# cpu.net
KiCad netlist of a schematic drawn in Altium Designer
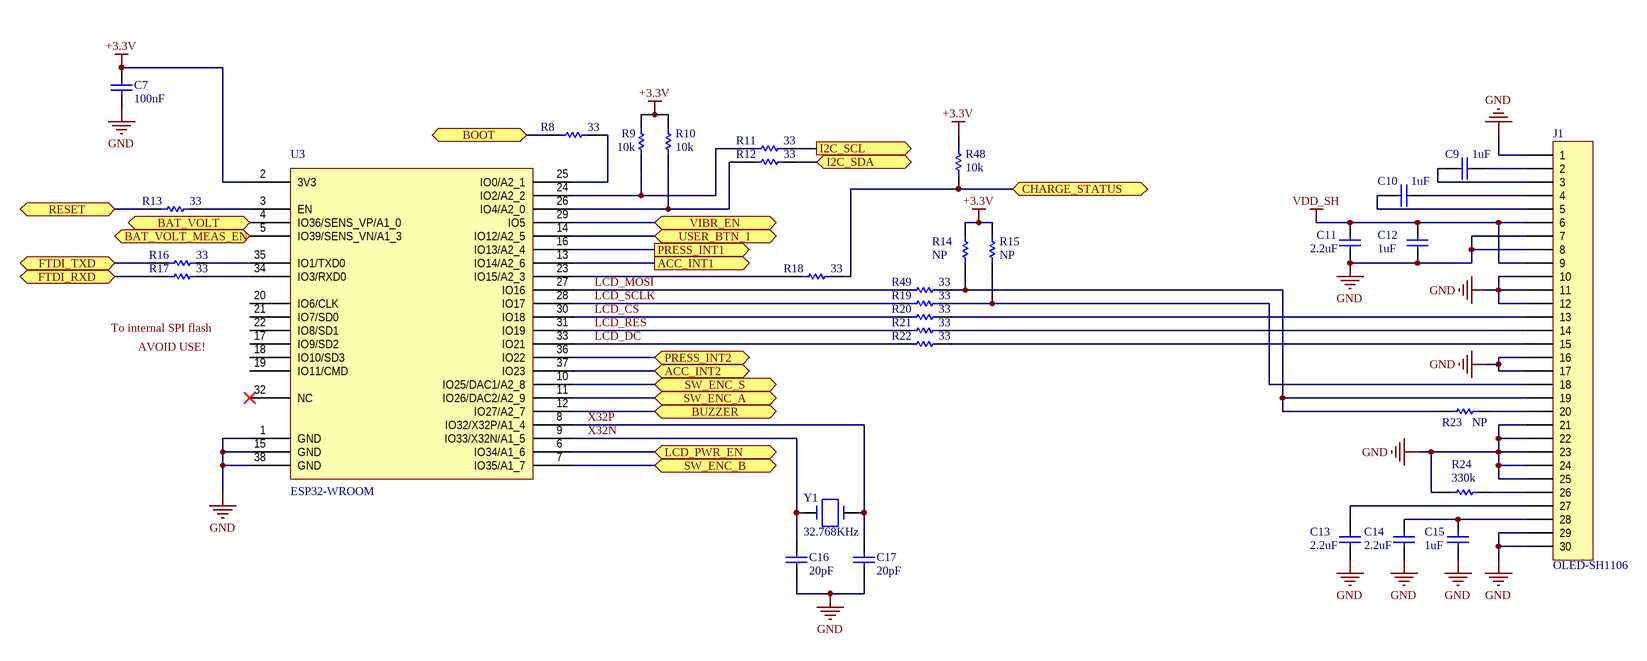
[diagram p0: cpu.SchDoc]

(export (version "E")
  (design (tool "Eeschema 10.0.6"))
  (components
    (comp (ref "C7")
      (value "100nF")
      (footprint "0402_[1005]")
      (description "Capacitor")
      (fields (field (name "PUBLISHER") "Altium Limited"))
      (libsource (lib "Miscellaneous Devices") (part "Cap"))
    )
    (comp (ref "C9")
      (value "1uF")
      (footprint "0603_[1608]")
      (description "Capacitor")
      (fields (field (name "PUBLISHER") "Altium Limited"))
      (libsource (lib "develer_library") (part "Cap"))
    )
    (comp (ref "C10")
      (value "1uF")
      (footprint "0603_[1608]")
      (description "Capacitor")
      (fields (field (name "PUBLISHER") "Altium Limited"))
      (libsource (lib "develer_library") (part "Cap"))
    )
    (comp (ref "C11")
      (value "2.2uF")
      (footprint "0603_[1608]")
      (description "Capacitor")
      (fields (field (name "PUBLISHER") "Altium Limited"))
      (libsource (lib "develer_library") (part "Cap"))
    )
    (comp (ref "C12")
      (value "1uF")
      (footprint "0603_[1608]")
      (description "Capacitor")
      (fields (field (name "PUBLISHER") "Altium Limited"))
      (libsource (lib "develer_library") (part "Cap"))
    )
    (comp (ref "C13")
      (value "2.2uF")
      (footprint "0603_[1608]")
      (description "Capacitor")
      (fields (field (name "PUBLISHER") "Altium Limited"))
      (libsource (lib "develer_library") (part "Cap"))
    )
    (comp (ref "C14")
      (value "2.2uF")
      (footprint "0603_[1608]")
      (description "Capacitor")
      (fields (field (name "PUBLISHER") "Altium Limited"))
      (libsource (lib "develer_library") (part "Cap"))
    )
    (comp (ref "C15")
      (value "1uF")
      (footprint "0603_[1608]")
      (description "Capacitor")
      (fields (field (name "PUBLISHER") "Altium Limited"))
      (libsource (lib "develer_library") (part "Cap"))
    )
    (comp (ref "C16")
      (value "20pF")
      (footprint "0402_[1005]")
      (description "Capacitor")
      (fields (field (name "PUBLISHER") "Altium Limited"))
      (libsource (lib "develer_library") (part "Cap"))
    )
    (comp (ref "C17")
      (value "20pF")
      (footprint "0402_[1005]")
      (description "Capacitor")
      (fields (field (name "PUBLISHER") "Altium Limited"))
      (libsource (lib "develer_library") (part "Cap"))
    )
    (comp (ref "J1")
      (value "OLED-SH1106")
      (footprint "flat_30pin_0,7mm")
      (description "Header, 30-Pin")
      (fields (field (name "PUBLISHER") "Altium Limited"))
      (libsource (lib "Miscellaneous Connectors") (part "Header 30"))
    )
    (comp (ref "R8")
      (value "33")
      (footprint "0402_[1005]")
      (description "Resistor")
      (fields (field (name "PUBLISHER") "Altium Limited"))
      (libsource (lib "Miscellaneous Devices") (part "Res1"))
    )
    (comp (ref "R9")
      (value "10k")
      (footprint "0402_[1005]")
      (description "Resistor")
      (fields (field (name "PUBLISHER") "Altium Limited"))
      (libsource (lib "Miscellaneous Devices") (part "Res1"))
    )
    (comp (ref "R10")
      (value "10k")
      (footprint "0402_[1005]")
      (description "Resistor")
      (fields (field (name "PUBLISHER") "Altium Limited"))
      (libsource (lib "Miscellaneous Devices") (part "Res1"))
    )
    (comp (ref "R11")
      (value "33")
      (footprint "0402_[1005]")
      (description "Resistor")
      (fields (field (name "PUBLISHER") "Altium Limited"))
      (libsource (lib "Miscellaneous Devices") (part "Res1"))
    )
    (comp (ref "R12")
      (value "33")
      (footprint "0402_[1005]")
      (description "Resistor")
      (fields (field (name "PUBLISHER") "Altium Limited"))
      (libsource (lib "Miscellaneous Devices") (part "Res1"))
    )
    (comp (ref "R13")
      (value "33")
      (footprint "0402_[1005]")
      (description "Resistor")
      (fields (field (name "PUBLISHER") "Altium Limited"))
      (libsource (lib "Miscellaneous Devices") (part "Res1"))
    )
    (comp (ref "R14")
      (value "NP")
      (footprint "0402_[1005]")
      (description "Resistor")
      (fields (field (name "PUBLISHER") "Altium Limited"))
      (libsource (lib "Miscellaneous Devices") (part "Res1"))
    )
    (comp (ref "R15")
      (value "NP")
      (footprint "0402_[1005]")
      (description "Resistor")
      (fields (field (name "PUBLISHER") "Altium Limited"))
      (libsource (lib "Miscellaneous Devices") (part "Res1"))
    )
    (comp (ref "R16")
      (value "33")
      (footprint "0402_[1005]")
      (description "Resistor")
      (fields (field (name "PUBLISHER") "Altium Limited"))
      (libsource (lib "Miscellaneous Devices") (part "Res1"))
    )
    (comp (ref "R17")
      (value "33")
      (footprint "0402_[1005]")
      (description "Resistor")
      (fields (field (name "PUBLISHER") "Altium Limited"))
      (libsource (lib "Miscellaneous Devices") (part "Res1"))
    )
    (comp (ref "R18")
      (value "33")
      (footprint "0402_[1005]")
      (description "Resistor")
      (fields (field (name "PUBLISHER") "Altium Limited"))
      (libsource (lib "Miscellaneous Devices") (part "Res1"))
    )
    (comp (ref "R19")
      (value "33")
      (footprint "0402_[1005]")
      (description "Resistor")
      (fields (field (name "PUBLISHER") "Altium Limited"))
      (libsource (lib "Miscellaneous Devices") (part "Res1"))
    )
    (comp (ref "R20")
      (value "33")
      (footprint "0402_[1005]")
      (description "Resistor")
      (fields (field (name "PUBLISHER") "Altium Limited"))
      (libsource (lib "Miscellaneous Devices") (part "Res1"))
    )
    (comp (ref "R21")
      (value "33")
      (footprint "0402_[1005]")
      (description "Resistor")
      (fields (field (name "PUBLISHER") "Altium Limited"))
      (libsource (lib "Miscellaneous Devices") (part "Res1"))
    )
    (comp (ref "R22")
      (value "33")
      (footprint "0402_[1005]")
      (description "Resistor")
      (fields (field (name "PUBLISHER") "Altium Limited"))
      (libsource (lib "Miscellaneous Devices") (part "Res1"))
    )
    (comp (ref "R23")
      (value "NP")
      (footprint "0402_[1005]")
      (description "Resistor")
      (fields (field (name "PUBLISHER") "Altium Limited"))
      (libsource (lib "Miscellaneous Devices") (part "Res1"))
    )
    (comp (ref "R24")
      (value "330k")
      (footprint "0402_[1005]")
      (description "Resistor")
      (fields (field (name "PUBLISHER") "Altium Limited"))
      (libsource (lib "Miscellaneous Devices") (part "Res1"))
    )
    (comp (ref "R48")
      (value "10k")
      (footprint "0402_[1005]")
      (description "Resistor")
      (fields (field (name "PUBLISHER") "Altium Limited"))
      (libsource (lib "Miscellaneous Devices") (part "Res1"))
    )
    (comp (ref "R49")
      (value "33")
      (footprint "0402_[1005]")
      (description "Resistor")
      (fields (field (name "PUBLISHER") "Altium Limited"))
      (libsource (lib "Miscellaneous Devices") (part "Res1"))
    )
    (comp (ref "U3")
      (value "ESP32-WROOM")
      (footprint "ESP-WROOM-32")
      (description "Wi-Fi+BT+BLE MCU module based on ESP32-D0WDQ6")
      (libsource (lib "develer_library") (part "ESP32-WROOM"))
    )
    (comp (ref "Y1")
      (value "32.768KHz")
      (footprint "CRYSTAL_3.2X1.5MM_2P_SMD")
      (description "Crystal 24 MHz SMT 25X2 Low Profile")
      (fields (field (name "PART NUMBER") "Aker C2E-24.000-12-3030-X"))
      (libsource (lib "develer_library") (part "24MHZ-SMD"))
    )
  )
  (nets
    (net (code "1") (name "+3.3V") (class "Default")
      (node (ref "C7") (pin "2") (pinfunction "2_2") (pintype "passive"))
      (node (ref "R10") (pin "2") (pinfunction "2_2") (pintype "passive"))
      (node (ref "R14") (pin "2") (pinfunction "2_2") (pintype "passive"))
      (node (ref "R15") (pin "2") (pinfunction "2_2") (pintype "passive"))
      (node (ref "R48") (pin "2") (pinfunction "2_2") (pintype "passive"))
      (node (ref "R9") (pin "2") (pinfunction "2_2") (pintype "passive"))
      (node (ref "U3") (pin "2") (pinfunction "3V3_2") (pintype "passive"))
    )
    (net (code "2") (name "/ACC_INT1") (class "Default")
      (node (ref "U3") (pin "13") (pinfunction "IO14/A2_6_13") (pintype "passive"))
    )
    (net (code "3") (name "/ACC_INT2") (class "Default")
      (node (ref "U3") (pin "37") (pinfunction "IO23_37") (pintype "passive"))
    )
    (net (code "4") (name "/BAT_VOLT") (class "Default")
      (node (ref "U3") (pin "4") (pinfunction "IO36/SENS_VP/A1_0_4") (pintype "passive"))
    )
    (net (code "5") (name "/BAT_VOLT_MEAS_EN") (class "Default")
      (node (ref "U3") (pin "5") (pinfunction "IO39/SENS_VN/A1_3_5") (pintype "passive"))
    )
    (net (code "6") (name "/BOOT") (class "Default")
      (node (ref "R8") (pin "1") (pinfunction "1_1") (pintype "passive"))
    )
    (net (code "7") (name "/BUZZER") (class "Default")
      (node (ref "U3") (pin "12") (pinfunction "IO27/A2_7_12") (pintype "passive"))
    )
    (net (code "8") (name "/CHARGE_STATUS") (class "Default")
      (node (ref "R18") (pin "2") (pinfunction "2_2") (pintype "passive"))
      (node (ref "R48") (pin "1") (pinfunction "1_1") (pintype "passive"))
    )
    (net (code "9") (name "/FTDI_RXD") (class "Default")
      (node (ref "R17") (pin "1") (pinfunction "1_1") (pintype "passive"))
    )
    (net (code "10") (name "/FTDI_TXD") (class "Default")
      (node (ref "R16") (pin "1") (pinfunction "1_1") (pintype "passive"))
    )
    (net (code "11") (name "/I2C_SCL") (class "Default")
      (node (ref "R11") (pin "2") (pinfunction "2_2") (pintype "passive"))
    )
    (net (code "12") (name "/I2C_SDA") (class "Default")
      (node (ref "R12") (pin "2") (pinfunction "2_2") (pintype "passive"))
    )
    (net (code "13") (name "/LCD_CS") (class "Default")
      (node (ref "R20") (pin "1") (pinfunction "1_1") (pintype "passive"))
      (node (ref "U3") (pin "30") (pinfunction "IO18_30") (pintype "passive"))
    )
    (net (code "14") (name "/LCD_DC") (class "Default")
      (node (ref "R22") (pin "1") (pinfunction "1_1") (pintype "passive"))
      (node (ref "U3") (pin "33") (pinfunction "IO21_33") (pintype "passive"))
    )
    (net (code "15") (name "/LCD_MOSI") (class "Default")
      (node (ref "R49") (pin "1") (pinfunction "1_1") (pintype "passive"))
      (node (ref "U3") (pin "27") (pinfunction "IO16_27") (pintype "passive"))
    )
    (net (code "16") (name "/LCD_PWR_EN") (class "Default")
      (node (ref "U3") (pin "6") (pinfunction "IO34/A1_6_6") (pintype "passive"))
    )
    (net (code "17") (name "/LCD_RES") (class "Default")
      (node (ref "R21") (pin "1") (pinfunction "1_1") (pintype "passive"))
      (node (ref "U3") (pin "31") (pinfunction "IO19_31") (pintype "passive"))
    )
    (net (code "18") (name "/LCD_SCLK") (class "Default")
      (node (ref "R19") (pin "1") (pinfunction "1_1") (pintype "passive"))
      (node (ref "U3") (pin "28") (pinfunction "IO17_28") (pintype "passive"))
    )
    (net (code "19") (name "/PRESS_INT1") (class "Default")
      (node (ref "U3") (pin "16") (pinfunction "IO13/A2_4_16") (pintype "passive"))
    )
    (net (code "20") (name "/PRESS_INT2") (class "Default")
      (node (ref "U3") (pin "36") (pinfunction "IO22_36") (pintype "passive"))
    )
    (net (code "21") (name "/RESET") (class "Default")
      (node (ref "R13") (pin "1") (pinfunction "1_1") (pintype "passive"))
    )
    (net (code "22") (name "/SW_ENC_A") (class "Default")
      (node (ref "U3") (pin "11") (pinfunction "IO26/DAC2/A2_9_11") (pintype "passive"))
    )
    (net (code "23") (name "/SW_ENC_B") (class "Default")
      (node (ref "U3") (pin "7") (pinfunction "IO35/A1_7_7") (pintype "passive"))
    )
    (net (code "24") (name "/SW_ENC_S") (class "Default")
      (node (ref "U3") (pin "10") (pinfunction "IO25/DAC1/A2_8_10") (pintype "passive"))
    )
    (net (code "25") (name "/USER_BTN_1") (class "Default")
      (node (ref "U3") (pin "14") (pinfunction "IO12/A2_5_14") (pintype "passive"))
    )
    (net (code "26") (name "/VIBR_EN") (class "Default")
      (node (ref "U3") (pin "29") (pinfunction "IO5_29") (pintype "passive"))
    )
    (net (code "27") (name "/X32N") (class "Default")
      (node (ref "C16") (pin "2") (pinfunction "2_2") (pintype "passive"))
      (node (ref "U3") (pin "9") (pinfunction "IO33/X32N/A1_5_9") (pintype "passive"))
      (node (ref "Y1") (pin "1") (pinfunction "1_1") (pintype "passive"))
    )
    (net (code "28") (name "/X32P") (class "Default")
      (node (ref "C17") (pin "2") (pinfunction "2_2") (pintype "passive"))
      (node (ref "U3") (pin "8") (pinfunction "IO32/X32P/A1_4_8") (pintype "passive"))
      (node (ref "Y1") (pin "2") (pinfunction "2_2") (pintype "passive"))
    )
    (net (code "29") (name "GND") (class "Default")
      (node (ref "C11") (pin "1") (pinfunction "1_1") (pintype "passive"))
      (node (ref "C12") (pin "1") (pinfunction "1_1") (pintype "passive"))
      (node (ref "C13") (pin "1") (pinfunction "1_1") (pintype "passive"))
      (node (ref "C14") (pin "1") (pinfunction "1_1") (pintype "passive"))
      (node (ref "C15") (pin "1") (pinfunction "1_1") (pintype "passive"))
      (node (ref "C16") (pin "1") (pinfunction "1_1") (pintype "passive"))
      (node (ref "C17") (pin "1") (pinfunction "1_1") (pintype "passive"))
      (node (ref "C7") (pin "1") (pinfunction "1_1") (pintype "passive"))
      (node (ref "J1") (pin "1") (pinfunction "1_1") (pintype "passive"))
      (node (ref "J1") (pin "10") (pinfunction "10_10") (pintype "passive"))
      (node (ref "J1") (pin "11") (pinfunction "11_11") (pintype "passive"))
      (node (ref "J1") (pin "12") (pinfunction "12_12") (pintype "passive"))
      (node (ref "J1") (pin "16") (pinfunction "16_16") (pintype "passive"))
      (node (ref "J1") (pin "17") (pinfunction "17_17") (pintype "passive"))
      (node (ref "J1") (pin "21") (pinfunction "21_21") (pintype "passive"))
      (node (ref "J1") (pin "22") (pinfunction "22_22") (pintype "passive"))
      (node (ref "J1") (pin "23") (pinfunction "23_23") (pintype "passive"))
      (node (ref "J1") (pin "24") (pinfunction "24_24") (pintype "passive"))
      (node (ref "J1") (pin "25") (pinfunction "25_25") (pintype "passive"))
      (node (ref "J1") (pin "29") (pinfunction "29_29") (pintype "passive"))
      (node (ref "J1") (pin "30") (pinfunction "30_30") (pintype "passive"))
      (node (ref "J1") (pin "7") (pinfunction "7_7") (pintype "passive"))
      (node (ref "J1") (pin "8") (pinfunction "8_8") (pintype "passive"))
      (node (ref "R24") (pin "2") (pinfunction "2_2") (pintype "passive"))
      (node (ref "U3") (pin "1") (pinfunction "GND_1") (pintype "passive"))
      (node (ref "U3") (pin "15") (pinfunction "GND_15") (pintype "passive"))
      (node (ref "U3") (pin "38") (pinfunction "GND_38") (pintype "passive"))
    )
    (net (code "30") (name "Net-(C9-Pad1)") (class "Default")
      (node (ref "C9") (pin "1") (pinfunction "1_1") (pintype "passive"))
      (node (ref "J1") (pin "2") (pinfunction "2_2") (pintype "passive"))
    )
    (net (code "31") (name "Net-(C9-Pad2)") (class "Default")
      (node (ref "C9") (pin "2") (pinfunction "2_2") (pintype "passive"))
      (node (ref "J1") (pin "3") (pinfunction "3_3") (pintype "passive"))
    )
    (net (code "32") (name "Net-(C10-Pad1)") (class "Default")
      (node (ref "C10") (pin "1") (pinfunction "1_1") (pintype "passive"))
      (node (ref "J1") (pin "4") (pinfunction "4_4") (pintype "passive"))
    )
    (net (code "33") (name "Net-(C10-Pad2)") (class "Default")
      (node (ref "C10") (pin "2") (pinfunction "2_2") (pintype "passive"))
      (node (ref "J1") (pin "5") (pinfunction "5_5") (pintype "passive"))
    )
    (net (code "34") (name "Net-(C13-Pad2)") (class "Default")
      (node (ref "C13") (pin "2") (pinfunction "2_2") (pintype "passive"))
      (node (ref "J1") (pin "27") (pinfunction "27_27") (pintype "passive"))
    )
    (net (code "35") (name "Net-(C14-Pad2)") (class "Default")
      (node (ref "C14") (pin "2") (pinfunction "2_2") (pintype "passive"))
      (node (ref "C15") (pin "2") (pinfunction "2_2") (pintype "passive"))
      (node (ref "J1") (pin "28") (pinfunction "28_28") (pintype "passive"))
    )
    (net (code "36") (name "Net-(J1-Pad13)") (class "Default")
      (node (ref "J1") (pin "13") (pinfunction "13_13") (pintype "passive"))
      (node (ref "R20") (pin "2") (pinfunction "2_2") (pintype "passive"))
    )
    (net (code "37") (name "Net-(J1-Pad14)") (class "Default")
      (node (ref "J1") (pin "14") (pinfunction "14_14") (pintype "passive"))
      (node (ref "R21") (pin "2") (pinfunction "2_2") (pintype "passive"))
    )
    (net (code "38") (name "Net-(J1-Pad15)") (class "Default")
      (node (ref "J1") (pin "15") (pinfunction "15_15") (pintype "passive"))
      (node (ref "R22") (pin "2") (pinfunction "2_2") (pintype "passive"))
    )
    (net (code "39") (name "Net-(J1-Pad18)") (class "Default")
      (node (ref "J1") (pin "18") (pinfunction "18_18") (pintype "passive"))
      (node (ref "R15") (pin "1") (pinfunction "1_1") (pintype "passive"))
      (node (ref "R19") (pin "2") (pinfunction "2_2") (pintype "passive"))
    )
    (net (code "40") (name "Net-(J1-Pad19)") (class "Default")
      (node (ref "J1") (pin "19") (pinfunction "19_19") (pintype "passive"))
      (node (ref "R14") (pin "1") (pinfunction "1_1") (pintype "passive"))
      (node (ref "R23") (pin "1") (pinfunction "1_1") (pintype "passive"))
      (node (ref "R49") (pin "2") (pinfunction "2_2") (pintype "passive"))
    )
    (net (code "41") (name "Net-(J1-Pad20)") (class "Default")
      (node (ref "J1") (pin "20") (pinfunction "20_20") (pintype "passive"))
      (node (ref "R23") (pin "2") (pinfunction "2_2") (pintype "passive"))
    )
    (net (code "42") (name "Net-(J1-Pad26)") (class "Default")
      (node (ref "J1") (pin "26") (pinfunction "26_26") (pintype "passive"))
      (node (ref "R24") (pin "1") (pinfunction "1_1") (pintype "passive"))
    )
    (net (code "43") (name "Net-(U3-EN)") (class "Default")
      (node (ref "R13") (pin "2") (pinfunction "2_2") (pintype "passive"))
      (node (ref "U3") (pin "3") (pinfunction "EN_3") (pintype "passive"))
    )
    (net (code "44") (name "Net-(U3-IO0{slash}A2_1)") (class "Default")
      (node (ref "R8") (pin "2") (pinfunction "2_2") (pintype "passive"))
      (node (ref "U3") (pin "25") (pinfunction "IO0/A2_1_25") (pintype "passive"))
    )
    (net (code "45") (name "Net-(U3-IO1{slash}TXD0)") (class "Default")
      (node (ref "R16") (pin "2") (pinfunction "2_2") (pintype "passive"))
      (node (ref "U3") (pin "35") (pinfunction "IO1/TXD0_35") (pintype "passive"))
    )
    (net (code "46") (name "Net-(U3-IO2{slash}A2_2)") (class "Default")
      (node (ref "R11") (pin "1") (pinfunction "1_1") (pintype "passive"))
      (node (ref "R9") (pin "1") (pinfunction "1_1") (pintype "passive"))
      (node (ref "U3") (pin "24") (pinfunction "IO2/A2_2_24") (pintype "passive"))
    )
    (net (code "47") (name "Net-(U3-IO3{slash}RXD0)") (class "Default")
      (node (ref "R17") (pin "2") (pinfunction "2_2") (pintype "passive"))
      (node (ref "U3") (pin "34") (pinfunction "IO3/RXD0_34") (pintype "passive"))
    )
    (net (code "48") (name "Net-(U3-IO4{slash}A2_0)") (class "Default")
      (node (ref "R10") (pin "1") (pinfunction "1_1") (pintype "passive"))
      (node (ref "R12") (pin "1") (pinfunction "1_1") (pintype "passive"))
      (node (ref "U3") (pin "26") (pinfunction "IO4/A2_0_26") (pintype "passive"))
    )
    (net (code "49") (name "Net-(U3-IO15{slash}A2_3)") (class "Default")
      (node (ref "R18") (pin "1") (pinfunction "1_1") (pintype "passive"))
      (node (ref "U3") (pin "23") (pinfunction "IO15/A2_3_23") (pintype "passive"))
    )
    (net (code "50") (name "VDD_SH") (class "Default")
      (node (ref "C11") (pin "2") (pinfunction "2_2") (pintype "passive"))
      (node (ref "C12") (pin "2") (pinfunction "2_2") (pintype "passive"))
      (node (ref "J1") (pin "6") (pinfunction "6_6") (pintype "passive"))
      (node (ref "J1") (pin "9") (pinfunction "9_9") (pintype "passive"))
    )
    (net (code "51") (name "unconnected-(U3-IO6{slash}CLK-Pad20)") (class "Default")
      (node (ref "U3") (pin "20") (pinfunction "IO6/CLK_20") (pintype "passive"))
    )
    (net (code "52") (name "unconnected-(U3-IO7{slash}SD0-Pad21)") (class "Default")
      (node (ref "U3") (pin "21") (pinfunction "IO7/SD0_21") (pintype "passive"))
    )
    (net (code "53") (name "unconnected-(U3-IO8{slash}SD1-Pad22)") (class "Default")
      (node (ref "U3") (pin "22") (pinfunction "IO8/SD1_22") (pintype "passive"))
    )
    (net (code "54") (name "unconnected-(U3-IO9{slash}SD2-Pad17)") (class "Default")
      (node (ref "U3") (pin "17") (pinfunction "IO9/SD2_17") (pintype "passive"))
    )
    (net (code "55") (name "unconnected-(U3-IO10{slash}SD3-Pad18)") (class "Default")
      (node (ref "U3") (pin "18") (pinfunction "IO10/SD3_18") (pintype "passive"))
    )
    (net (code "56") (name "unconnected-(U3-IO11{slash}CMD-Pad19)") (class "Default")
      (node (ref "U3") (pin "19") (pinfunction "IO11/CMD_19") (pintype "passive"))
    )
    (net (code "57") (name "unconnected-(U3-NC-Pad32)") (class "Default")
      (node (ref "U3") (pin "32") (pinfunction "NC_32") (pintype "passive+no_connect"))
    )
  )
)
